# Control_Signals.net
KiCad netlist of a schematic drawn in Altium Designer
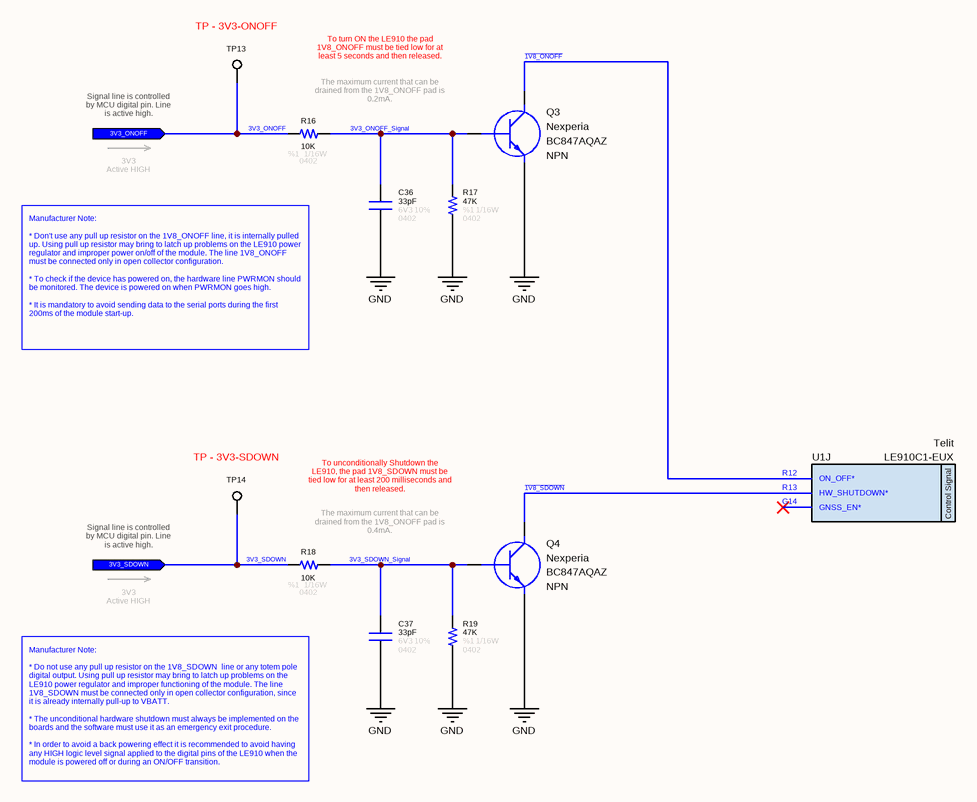
[diagram p0: Control_Signals.SchDoc]

(export (version "E")
  (design (tool "Eeschema 10.0.6"))
  (components
    (comp (ref "C36")
      (value "33pF")
      (footprint "CAPACITOR_0402")
      (description "Capacitor - 33pF [0402] (Ceramic)")
      (fields
        (field (name "MANUFACTURER PART NUMBER") "C0402C330J9RACAUTO")
        (field (name "TOLERANCE") "10%")
        (field (name "CASE") "0402")
        (field (name "VOLTAGE") "6V3")
      )
      (libsource (lib "Akkoyun") (part "Capacitor - 33pF [0402-6V3]"))
    )
    (comp (ref "C37")
      (value "33pF")
      (footprint "CAPACITOR_0402")
      (description "Capacitor - 33pF [0402] (Ceramic)")
      (fields
        (field (name "MANUFACTURER PART NUMBER") "C0402C330J9RACAUTO")
        (field (name "TOLERANCE") "10%")
        (field (name "CASE") "0402")
        (field (name "VOLTAGE") "6V3")
      )
      (libsource (lib "Akkoyun") (part "Capacitor - 33pF [0402-6V3]"))
    )
    (comp (ref "Q3")
      (value "BC847AQAZ")
      (footprint "SOT1215")
      (description "Bipolar NPN Transistors")
      (fields
        (field (name "MANUFACTURER NAME") "Nexperia")
        (field (name "MANUFACTURER PART NUMBER") "BC847AQAZ")
        (field (name "POLARITY") "NPN")
      )
      (libsource (lib "Akkoyun") (part "Transistor - BC847"))
    )
    (comp (ref "Q4")
      (value "BC847AQAZ")
      (footprint "SOT1215")
      (description "Bipolar NPN Transistors")
      (fields
        (field (name "MANUFACTURER NAME") "Nexperia")
        (field (name "MANUFACTURER PART NUMBER") "BC847AQAZ")
        (field (name "POLARITY") "NPN")
      )
      (libsource (lib "Akkoyun") (part "Transistor - BC847"))
    )
    (comp (ref "R16")
      (value "10K")
      (footprint "RESISTOR_0402")
      (description "Thick Film Resistors - SMD 1/16 W 10 KOhm 1%")
      (fields
        (field (name "MANUFACTURER PART NUMBER") "CRCW040210K0FKED")
        (field (name "TOLERANCE") "%1")
        (field (name "CASE") "0402")
        (field (name "POWER") "1/16W")
        (field (name "Comment") "10K - 0402 - %1 - 1/16W")
      )
      (libsource (lib "Akkoyun") (part "Resistor - 10K [0402]"))
    )
    (comp (ref "R17")
      (value "47K")
      (footprint "RESISTOR_0402")
      (description "Thick Film Resistors - SMD 1/16 W 47 KOhm 1%")
      (fields
        (field (name "MANUFACTURER PART NUMBER") "CRCW040247K0FKED")
        (field (name "TOLERANCE") "%1")
        (field (name "CASE") "0402")
        (field (name "POWER") "1/16W")
        (field (name "Comment") "47K - 0402 - %1 - 1/16W")
      )
      (libsource (lib "Akkoyun") (part "Resistor - 47K [0402]"))
    )
    (comp (ref "R18")
      (value "10K")
      (footprint "RESISTOR_0402")
      (description "Thick Film Resistors - SMD 1/16 W 10 KOhm 1%")
      (fields
        (field (name "MANUFACTURER PART NUMBER") "CRCW040210K0FKED")
        (field (name "TOLERANCE") "%1")
        (field (name "CASE") "0402")
        (field (name "POWER") "1/16W")
        (field (name "Comment") "10K - 0402 - %1 - 1/16W")
      )
      (libsource (lib "Akkoyun") (part "Resistor - 10K [0402]"))
    )
    (comp (ref "R19")
      (value "47K")
      (footprint "RESISTOR_0402")
      (description "Thick Film Resistors - SMD 1/16 W 47 KOhm 1%")
      (fields
        (field (name "MANUFACTURER PART NUMBER") "CRCW040247K0FKED")
        (field (name "TOLERANCE") "%1")
        (field (name "CASE") "0402")
        (field (name "POWER") "1/16W")
        (field (name "Comment") "47K - 0402 - %1 - 1/16W")
      )
      (libsource (lib "Akkoyun") (part "Resistor - 47K [0402]"))
    )
    (comp (ref "TP13")
      (value "TP - 3V3-ONOFF")
      (footprint "TP")
      (description "Test Point")
      (libsource (lib "Akkoyun") (part "PCB - Test Point"))
    )
    (comp (ref "TP14")
      (value "TP - 3V3-SDOWN")
      (footprint "TP")
      (description "Test Point")
      (libsource (lib "Akkoyun") (part "PCB - Test Point"))
    )
    (comp (ref "U1")
      (value "LE910C1-EUX LTE GSM Module")
      (footprint "LE910 GSM Modem")
      (description "Telit LE910C1-EUX LTE/2G GSM Module")
      (fields
        (field (name "MANUFACTURER PART NUMBER") "LE910C1-EUX")
        (field (name "MANUFACTURER NAME") "Telit")
      )
      (libsource (lib "Akkoyun") (part "IC - LE910C1-EUX"))
    )
  )
  (nets
    (net (code "1") (name "/3V3_ONOFF") (class "Default")
      (node (ref "R16") (pin "2") (pinfunction "2_2") (pintype "passive"))
      (node (ref "TP13") (pin "1") (pinfunction "1_1") (pintype "passive"))
    )
    (net (code "2") (name "/3V3_ONOFF_Signal") (class "Default")
      (node (ref "C36") (pin "2") (pinfunction "2_2") (pintype "passive"))
      (node (ref "Q3") (pin "1") (pinfunction "B_1") (pintype "passive"))
      (node (ref "R16") (pin "1") (pinfunction "1_1") (pintype "passive"))
      (node (ref "R17") (pin "2") (pinfunction "2_2") (pintype "passive"))
    )
    (net (code "3") (name "/3V3_SDOWN") (class "Default")
      (node (ref "R18") (pin "2") (pinfunction "2_2") (pintype "passive"))
      (node (ref "TP14") (pin "1") (pinfunction "1_1") (pintype "passive"))
    )
    (net (code "4") (name "/3V3_SDOWN_Signal") (class "Default")
      (node (ref "C37") (pin "2") (pinfunction "2_2") (pintype "passive"))
      (node (ref "Q4") (pin "1") (pinfunction "B_1") (pintype "passive"))
      (node (ref "R18") (pin "1") (pinfunction "1_1") (pintype "passive"))
      (node (ref "R19") (pin "2") (pinfunction "2_2") (pintype "passive"))
    )
    (net (code "5") (name "/~{1V8_ONOFF}") (class "Default")
      (node (ref "Q3") (pin "3") (pinfunction "C_3") (pintype "passive"))
      (node (ref "U1") (pin "R12") (pinfunction "ON_OFF*_R12") (pintype "passive"))
    )
    (net (code "6") (name "/~{1V8_SDOWN}") (class "Default")
      (node (ref "Q4") (pin "3") (pinfunction "C_3") (pintype "passive"))
      (node (ref "U1") (pin "R13") (pinfunction "HW_SHUTDOWN*_R13") (pintype "passive"))
    )
    (net (code "7") (name "GND") (class "Default")
      (node (ref "C36") (pin "1") (pinfunction "1_1") (pintype "passive"))
      (node (ref "C37") (pin "1") (pinfunction "1_1") (pintype "passive"))
      (node (ref "Q3") (pin "2") (pinfunction "E_2") (pintype "passive"))
      (node (ref "Q4") (pin "2") (pinfunction "E_2") (pintype "passive"))
      (node (ref "R17") (pin "1") (pinfunction "1_1") (pintype "passive"))
      (node (ref "R19") (pin "1") (pinfunction "1_1") (pintype "passive"))
    )
    (net (code "8") (name "unconnected-(U1J-GNSS_EN*-PadG14)") (class "Default")
      (node (ref "U1") (pin "G14") (pinfunction "GNSS_EN*_G14") (pintype "passive+no_connect"))
    )
  )
)
